# E_Tactile_Display.net
KiCad netlist of a schematic drawn in Altium Designer
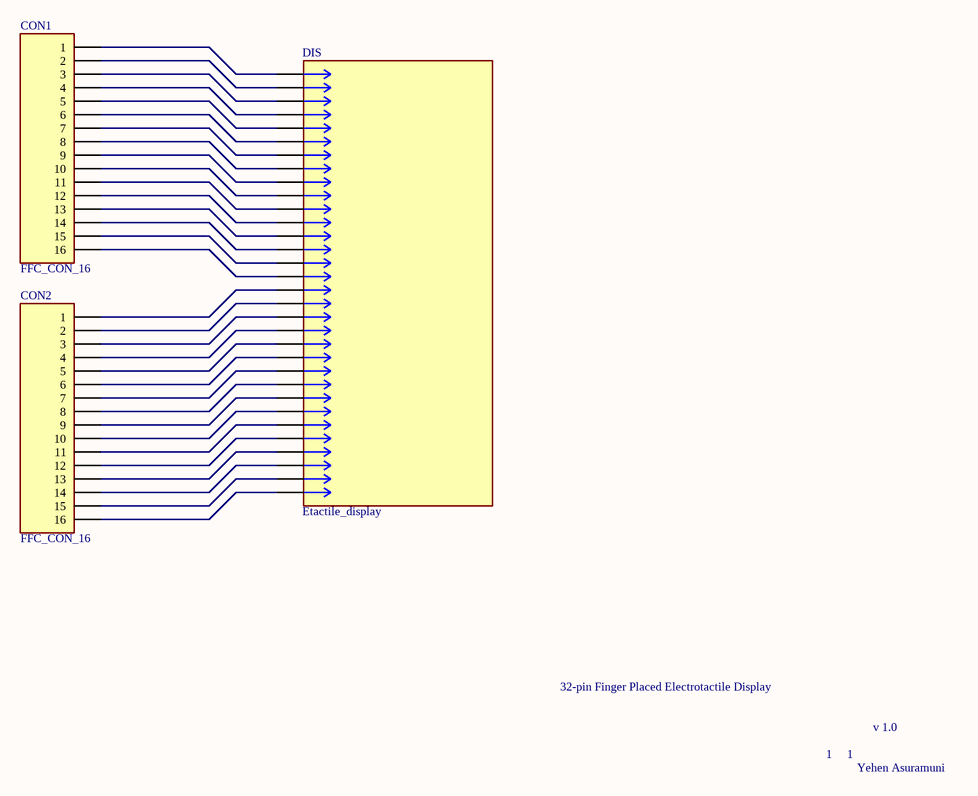
[diagram p0: E_Tactile_Display.SchDoc]

(export (version "E")
  (design (tool "Eeschema 10.0.6"))
  (components
    (comp (ref "CON1")
      (value "FFC_CON_16")
      (footprint "16_pin_smd_connector_pads")
      (libsource (lib "Etactile_Connector") (part "FFC_CON_16"))
    )
    (comp (ref "CON2")
      (value "FFC_CON_16")
      (footprint "16_pin_smd_connector_pads")
      (libsource (lib "Etactile_Connector") (part "FFC_CON_16"))
    )
    (comp (ref "DIS")
      (value "Etactile_display")
      (footprint "Electrode_Display")
      (libsource (lib "Etactile_Connector") (part "Etactile_display"))
    )
  )
  (nets
    (net (code "1") (name "Net-(CON1-Pad2)") (class "Default")
      (node (ref "CON1") (pin "2") (pinfunction "2_2") (pintype "passive"))
      (node (ref "DIS") (pin "1") (pinfunction "1_1") (pintype "passive"))
    )
    (net (code "2") (name "Net-(CON1-Pad3)") (class "Default")
      (node (ref "CON1") (pin "3") (pinfunction "3_3") (pintype "passive"))
      (node (ref "DIS") (pin "2") (pinfunction "2_2") (pintype "passive"))
    )
    (net (code "3") (name "Net-(CON1-Pad4)") (class "Default")
      (node (ref "CON1") (pin "4") (pinfunction "4_4") (pintype "passive"))
      (node (ref "DIS") (pin "3") (pinfunction "3_3") (pintype "passive"))
    )
    (net (code "4") (name "Net-(CON1-Pad5)") (class "Default")
      (node (ref "CON1") (pin "5") (pinfunction "5_5") (pintype "passive"))
      (node (ref "DIS") (pin "4") (pinfunction "4_4") (pintype "passive"))
    )
    (net (code "5") (name "Net-(CON1-Pad6)") (class "Default")
      (node (ref "CON1") (pin "6") (pinfunction "6_6") (pintype "passive"))
      (node (ref "DIS") (pin "5") (pinfunction "5_5") (pintype "passive"))
    )
    (net (code "6") (name "Net-(CON1-Pad7)") (class "Default")
      (node (ref "CON1") (pin "7") (pinfunction "7_7") (pintype "passive"))
      (node (ref "DIS") (pin "6") (pinfunction "6_6") (pintype "passive"))
    )
    (net (code "7") (name "Net-(CON1-Pad8)") (class "Default")
      (node (ref "CON1") (pin "8") (pinfunction "8_8") (pintype "passive"))
      (node (ref "DIS") (pin "7") (pinfunction "7_7") (pintype "passive"))
    )
    (net (code "8") (name "Net-(CON1-Pad9)") (class "Default")
      (node (ref "CON1") (pin "9") (pinfunction "9_9") (pintype "passive"))
      (node (ref "DIS") (pin "8") (pinfunction "8_8") (pintype "passive"))
    )
    (net (code "9") (name "Net-(CON1-Pad10)") (class "Default")
      (node (ref "CON1") (pin "10") (pinfunction "10_10") (pintype "passive"))
      (node (ref "DIS") (pin "9") (pinfunction "9_9") (pintype "passive"))
    )
    (net (code "10") (name "Net-(CON1-Pad11)") (class "Default")
      (node (ref "CON1") (pin "11") (pinfunction "11_11") (pintype "passive"))
      (node (ref "DIS") (pin "10") (pinfunction "10_10") (pintype "passive"))
    )
    (net (code "11") (name "Net-(CON1-Pad12)") (class "Default")
      (node (ref "CON1") (pin "12") (pinfunction "12_12") (pintype "passive"))
      (node (ref "DIS") (pin "11") (pinfunction "11_11") (pintype "passive"))
    )
    (net (code "12") (name "Net-(CON1-Pad13)") (class "Default")
      (node (ref "CON1") (pin "13") (pinfunction "13_13") (pintype "passive"))
      (node (ref "DIS") (pin "12") (pinfunction "12_12") (pintype "passive"))
    )
    (net (code "13") (name "Net-(CON1-Pad14)") (class "Default")
      (node (ref "CON1") (pin "14") (pinfunction "14_14") (pintype "passive"))
      (node (ref "DIS") (pin "13") (pinfunction "13_13") (pintype "passive"))
    )
    (net (code "14") (name "Net-(CON1-Pad15)") (class "Default")
      (node (ref "CON1") (pin "15") (pinfunction "15_15") (pintype "passive"))
      (node (ref "DIS") (pin "14") (pinfunction "14_14") (pintype "passive"))
    )
    (net (code "15") (name "Net-(CON1-Pad16)") (class "Default")
      (node (ref "CON1") (pin "16") (pinfunction "16_16") (pintype "passive"))
      (node (ref "DIS") (pin "15") (pinfunction "15_15") (pintype "passive"))
    )
    (net (code "16") (name "Net-(CON2-Pad1)") (class "Default")
      (node (ref "CON2") (pin "1") (pinfunction "1_1") (pintype "passive"))
      (node (ref "DIS") (pin "16") (pinfunction "16_16") (pintype "passive"))
    )
    (net (code "17") (name "Net-(CON2-Pad2)") (class "Default")
      (node (ref "CON2") (pin "2") (pinfunction "2_2") (pintype "passive"))
      (node (ref "DIS") (pin "17") (pinfunction "17_17") (pintype "passive"))
    )
    (net (code "18") (name "Net-(CON2-Pad3)") (class "Default")
      (node (ref "CON2") (pin "3") (pinfunction "3_3") (pintype "passive"))
      (node (ref "DIS") (pin "18") (pinfunction "18_18") (pintype "passive"))
    )
    (net (code "19") (name "Net-(CON2-Pad4)") (class "Default")
      (node (ref "CON2") (pin "4") (pinfunction "4_4") (pintype "passive"))
      (node (ref "DIS") (pin "19") (pinfunction "19_19") (pintype "passive"))
    )
    (net (code "20") (name "Net-(CON2-Pad5)") (class "Default")
      (node (ref "CON2") (pin "5") (pinfunction "5_5") (pintype "passive"))
      (node (ref "DIS") (pin "20") (pinfunction "20_20") (pintype "passive"))
    )
    (net (code "21") (name "Net-(CON2-Pad6)") (class "Default")
      (node (ref "CON2") (pin "6") (pinfunction "6_6") (pintype "passive"))
      (node (ref "DIS") (pin "21") (pinfunction "21_21") (pintype "passive"))
    )
    (net (code "22") (name "Net-(CON2-Pad7)") (class "Default")
      (node (ref "CON2") (pin "7") (pinfunction "7_7") (pintype "passive"))
      (node (ref "DIS") (pin "22") (pinfunction "22_22") (pintype "passive"))
    )
    (net (code "23") (name "Net-(CON2-Pad8)") (class "Default")
      (node (ref "CON2") (pin "8") (pinfunction "8_8") (pintype "passive"))
      (node (ref "DIS") (pin "23") (pinfunction "23_23") (pintype "passive"))
    )
    (net (code "24") (name "Net-(CON2-Pad9)") (class "Default")
      (node (ref "CON2") (pin "9") (pinfunction "9_9") (pintype "passive"))
      (node (ref "DIS") (pin "24") (pinfunction "24_24") (pintype "passive"))
    )
    (net (code "25") (name "Net-(CON2-Pad10)") (class "Default")
      (node (ref "CON2") (pin "10") (pinfunction "10_10") (pintype "passive"))
      (node (ref "DIS") (pin "25") (pinfunction "25_25") (pintype "passive"))
    )
    (net (code "26") (name "Net-(CON2-Pad11)") (class "Default")
      (node (ref "CON2") (pin "11") (pinfunction "11_11") (pintype "passive"))
      (node (ref "DIS") (pin "26") (pinfunction "26_26") (pintype "passive"))
    )
    (net (code "27") (name "Net-(CON2-Pad12)") (class "Default")
      (node (ref "CON2") (pin "12") (pinfunction "12_12") (pintype "passive"))
      (node (ref "DIS") (pin "27") (pinfunction "27_27") (pintype "passive"))
    )
    (net (code "28") (name "Net-(CON2-Pad13)") (class "Default")
      (node (ref "CON2") (pin "13") (pinfunction "13_13") (pintype "passive"))
      (node (ref "DIS") (pin "28") (pinfunction "28_28") (pintype "passive"))
    )
    (net (code "29") (name "Net-(CON2-Pad14)") (class "Default")
      (node (ref "CON2") (pin "14") (pinfunction "14_14") (pintype "passive"))
      (node (ref "DIS") (pin "29") (pinfunction "29_29") (pintype "passive"))
    )
    (net (code "30") (name "Net-(CON2-Pad15)") (class "Default")
      (node (ref "CON2") (pin "15") (pinfunction "15_15") (pintype "passive"))
      (node (ref "DIS") (pin "30") (pinfunction "30_30") (pintype "passive"))
    )
    (net (code "31") (name "Net-(CON2-Pad16)") (class "Default")
      (node (ref "CON2") (pin "16") (pinfunction "16_16") (pintype "passive"))
      (node (ref "DIS") (pin "31") (pinfunction "31_31") (pintype "passive"))
    )
    (net (code "32") (name "Net-(DIS-32)") (class "Default")
      (node (ref "CON1") (pin "1") (pinfunction "1_1") (pintype "passive"))
      (node (ref "DIS") (pin "0") (pinfunction "32_0") (pintype "passive"))
    )
  )
)
